# untitled.net
KiCad netlist of a schematic drawn in EAGLE
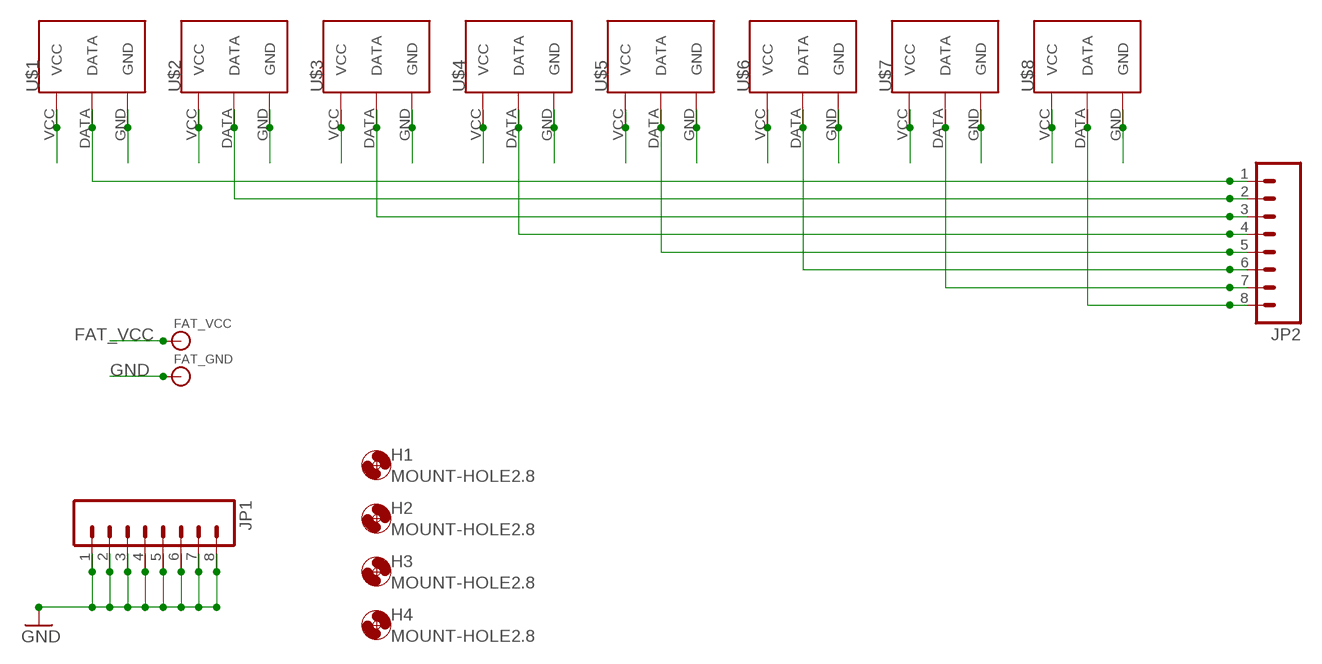
[diagram p0: schematic, sheet 1]

(export (version "E")
  (design (tool "Eeschema 10.0.6"))
  (components
    (comp (ref "FAT_GND")
      (value "BANANA_CONN")
      (footprint "eagle-import:BANANA_CONN")
      (libsource (lib "eagle-import") (part "BANANA_CONN"))
    )
    (comp (ref "FAT_VCC")
      (value "BANANA_CONN")
      (footprint "eagle-import:BANANA_CONN")
      (libsource (lib "eagle-import") (part "BANANA_CONN"))
    )
    (comp (ref "H1")
      (value "MOUNT-HOLE2.8")
      (footprint "eagle-import:2,8")
      (libsource (lib "eagle-import") (part "MOUNT-HOLE2.8"))
    )
    (comp (ref "H2")
      (value "MOUNT-HOLE2.8")
      (footprint "eagle-import:2,8")
      (libsource (lib "eagle-import") (part "MOUNT-HOLE2.8"))
    )
    (comp (ref "H3")
      (value "MOUNT-HOLE2.8")
      (footprint "eagle-import:2,8")
      (libsource (lib "eagle-import") (part "MOUNT-HOLE2.8"))
    )
    (comp (ref "H4")
      (value "MOUNT-HOLE2.8")
      (footprint "eagle-import:2,8")
      (libsource (lib "eagle-import") (part "MOUNT-HOLE2.8"))
    )
    (comp (ref "JP1")
      (value "M081X08")
      (footprint "eagle-import:1X08")
      (libsource (lib "eagle-import") (part "M081X08"))
    )
    (comp (ref "JP2")
      (value "M081X08")
      (footprint "eagle-import:1X08")
      (libsource (lib "eagle-import") (part "M081X08"))
    )
    (comp (ref "U$1")
      (value "OSTOQ035450")
      (footprint "eagle-import:OSTOQ035450")
      (libsource (lib "eagle-import") (part "OSTOQ035450"))
    )
    (comp (ref "U$2")
      (value "OSTOQ035450")
      (footprint "eagle-import:OSTOQ035450")
      (libsource (lib "eagle-import") (part "OSTOQ035450"))
    )
    (comp (ref "U$3")
      (value "OSTOQ035450")
      (footprint "eagle-import:OSTOQ035450")
      (libsource (lib "eagle-import") (part "OSTOQ035450"))
    )
    (comp (ref "U$4")
      (value "OSTOQ035450")
      (footprint "eagle-import:OSTOQ035450")
      (libsource (lib "eagle-import") (part "OSTOQ035450"))
    )
    (comp (ref "U$5")
      (value "OSTOQ035450")
      (footprint "eagle-import:OSTOQ035450")
      (libsource (lib "eagle-import") (part "OSTOQ035450"))
    )
    (comp (ref "U$6")
      (value "OSTOQ035450")
      (footprint "eagle-import:OSTOQ035450")
      (libsource (lib "eagle-import") (part "OSTOQ035450"))
    )
    (comp (ref "U$7")
      (value "OSTOQ035450")
      (footprint "eagle-import:OSTOQ035450")
      (libsource (lib "eagle-import") (part "OSTOQ035450"))
    )
    (comp (ref "U$8")
      (value "OSTOQ035450")
      (footprint "eagle-import:OSTOQ035450")
      (libsource (lib "eagle-import") (part "OSTOQ035450"))
    )
  )
  (nets
    (net (code "1") (name "/FAT_VCC") (class "Default")
      (node (ref "FAT_VCC") (pin "P$1") (pinfunction "1_P$1") (pintype "passive"))
      (node (ref "U$1") (pin "VCC") (pinfunction "VCC_VCC") (pintype "bidirectional"))
      (node (ref "U$2") (pin "VCC") (pinfunction "VCC_VCC") (pintype "bidirectional"))
      (node (ref "U$3") (pin "VCC") (pinfunction "VCC_VCC") (pintype "bidirectional"))
      (node (ref "U$4") (pin "VCC") (pinfunction "VCC_VCC") (pintype "bidirectional"))
      (node (ref "U$5") (pin "VCC") (pinfunction "VCC_VCC") (pintype "bidirectional"))
      (node (ref "U$6") (pin "VCC") (pinfunction "VCC_VCC") (pintype "bidirectional"))
      (node (ref "U$7") (pin "VCC") (pinfunction "VCC_VCC") (pintype "bidirectional"))
      (node (ref "U$8") (pin "VCC") (pinfunction "VCC_VCC") (pintype "bidirectional"))
    )
    (net (code "2") (name "GND") (class "Default")
      (node (ref "FAT_GND") (pin "P$1") (pinfunction "1_P$1") (pintype "passive"))
      (node (ref "JP1") (pin "1") (pinfunction "1_1") (pintype "passive"))
      (node (ref "JP1") (pin "2") (pinfunction "2_2") (pintype "passive"))
      (node (ref "JP1") (pin "3") (pinfunction "3_3") (pintype "passive"))
      (node (ref "JP1") (pin "4") (pinfunction "4_4") (pintype "passive"))
      (node (ref "JP1") (pin "5") (pinfunction "5_5") (pintype "passive"))
      (node (ref "JP1") (pin "6") (pinfunction "6_6") (pintype "passive"))
      (node (ref "JP1") (pin "7") (pinfunction "7_7") (pintype "passive"))
      (node (ref "JP1") (pin "8") (pinfunction "8_8") (pintype "passive"))
      (node (ref "U$1") (pin "GND") (pinfunction "GND_GND") (pintype "bidirectional"))
      (node (ref "U$2") (pin "GND") (pinfunction "GND_GND") (pintype "bidirectional"))
      (node (ref "U$3") (pin "GND") (pinfunction "GND_GND") (pintype "bidirectional"))
      (node (ref "U$4") (pin "GND") (pinfunction "GND_GND") (pintype "bidirectional"))
      (node (ref "U$5") (pin "GND") (pinfunction "GND_GND") (pintype "bidirectional"))
      (node (ref "U$6") (pin "GND") (pinfunction "GND_GND") (pintype "bidirectional"))
      (node (ref "U$7") (pin "GND") (pinfunction "GND_GND") (pintype "bidirectional"))
      (node (ref "U$8") (pin "GND") (pinfunction "GND_GND") (pintype "bidirectional"))
    )
    (net (code "3") (name "Net-(JP2-Pad1)") (class "Default")
      (node (ref "JP2") (pin "1") (pinfunction "1_1") (pintype "passive"))
      (node (ref "U$1") (pin "DATA") (pinfunction "DATA_DATA") (pintype "bidirectional"))
    )
    (net (code "4") (name "Net-(JP2-Pad2)") (class "Default")
      (node (ref "JP2") (pin "2") (pinfunction "2_2") (pintype "passive"))
      (node (ref "U$2") (pin "DATA") (pinfunction "DATA_DATA") (pintype "bidirectional"))
    )
    (net (code "5") (name "Net-(JP2-Pad3)") (class "Default")
      (node (ref "JP2") (pin "3") (pinfunction "3_3") (pintype "passive"))
      (node (ref "U$3") (pin "DATA") (pinfunction "DATA_DATA") (pintype "bidirectional"))
    )
    (net (code "6") (name "Net-(JP2-Pad4)") (class "Default")
      (node (ref "JP2") (pin "4") (pinfunction "4_4") (pintype "passive"))
      (node (ref "U$4") (pin "DATA") (pinfunction "DATA_DATA") (pintype "bidirectional"))
    )
    (net (code "7") (name "Net-(JP2-Pad5)") (class "Default")
      (node (ref "JP2") (pin "5") (pinfunction "5_5") (pintype "passive"))
      (node (ref "U$5") (pin "DATA") (pinfunction "DATA_DATA") (pintype "bidirectional"))
    )
    (net (code "8") (name "Net-(JP2-Pad6)") (class "Default")
      (node (ref "JP2") (pin "6") (pinfunction "6_6") (pintype "passive"))
      (node (ref "U$6") (pin "DATA") (pinfunction "DATA_DATA") (pintype "bidirectional"))
    )
    (net (code "9") (name "Net-(JP2-Pad7)") (class "Default")
      (node (ref "JP2") (pin "7") (pinfunction "7_7") (pintype "passive"))
      (node (ref "U$7") (pin "DATA") (pinfunction "DATA_DATA") (pintype "bidirectional"))
    )
    (net (code "10") (name "Net-(JP2-Pad8)") (class "Default")
      (node (ref "JP2") (pin "8") (pinfunction "8_8") (pintype "passive"))
      (node (ref "U$8") (pin "DATA") (pinfunction "DATA_DATA") (pintype "bidirectional"))
    )
  )
)
